# Li_Power_Boost_Converter.net
KiCad netlist of a schematic drawn in EAGLE
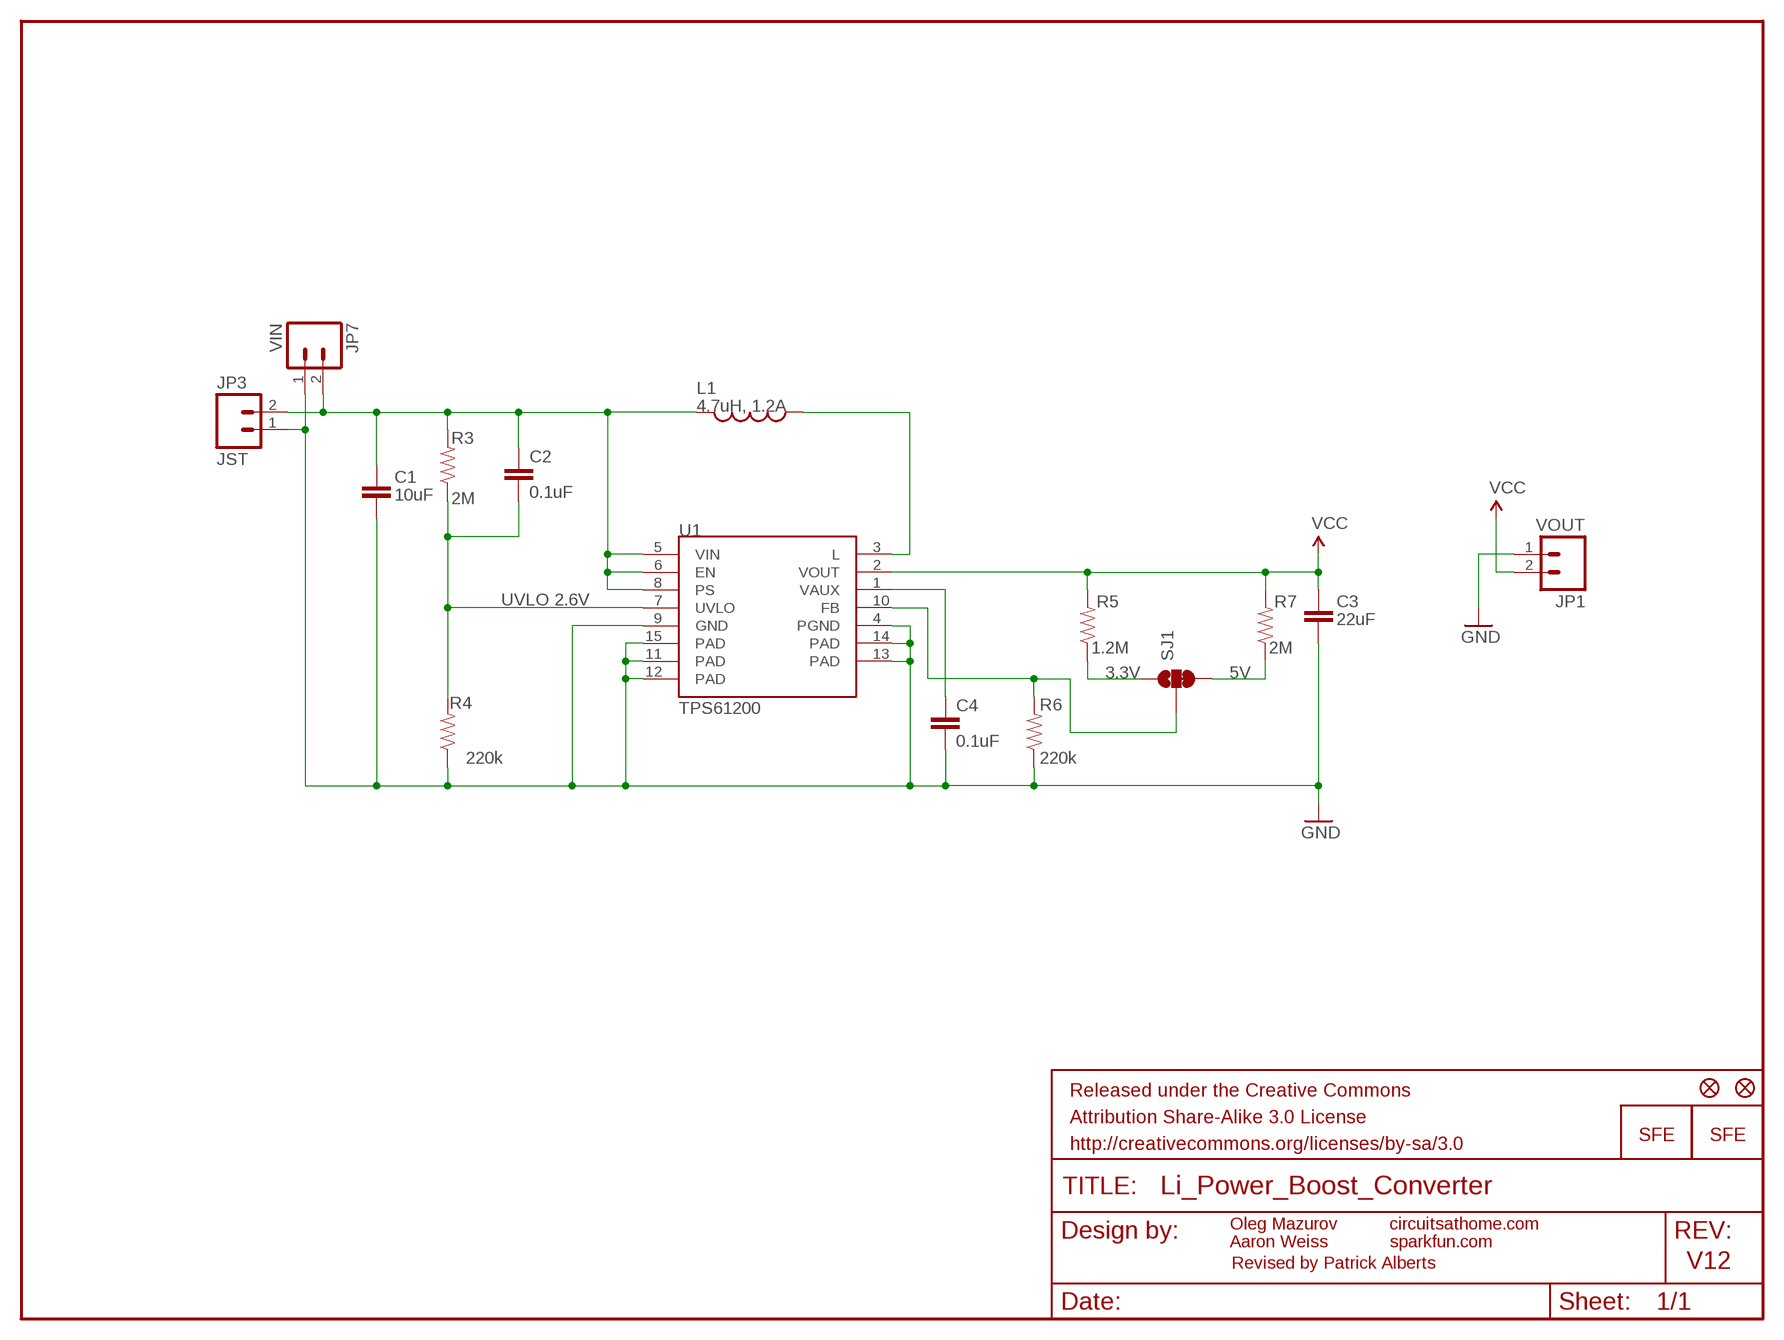
[diagram p0: schematic, sheet 1]

(export (version "E")
  (design (tool "Eeschema 10.0.6"))
  (components
    (comp (ref "C1")
      (value "10uF")
      (footprint "eagle-import:1206")
      (libsource (lib "eagle-import") (part "CAP1206"))
    )
    (comp (ref "C2")
      (value "0.1uF")
      (footprint "eagle-import:0603-CAP")
      (libsource (lib "eagle-import") (part "CAP0603-CAP"))
    )
    (comp (ref "C3")
      (value "22uF")
      (footprint "eagle-import:0805")
      (libsource (lib "eagle-import") (part "CAP0805"))
    )
    (comp (ref "C4")
      (value "0.1uF")
      (footprint "eagle-import:0603-CAP")
      (libsource (lib "eagle-import") (part "CAP0603-CAP"))
    )
    (comp (ref "FRAME1")
      (value "FRAME-LETTER")
      (footprint "eagle-import:CREATIVE_COMMONS")
      (libsource (lib "eagle-import") (part "FRAME-LETTER"))
    )
    (comp (ref "JP1")
      (value "VOUT")
      (footprint "eagle-import:1X02")
      (libsource (lib "eagle-import") (part "M02PTH"))
    )
    (comp (ref "JP2")
      (value "LOGO-SFESK")
      (footprint "eagle-import:SFE-LOGO-FLAME")
      (libsource (lib "eagle-import") (part "LOGO-SFESK"))
    )
    (comp (ref "JP3")
      (value "JST")
      (footprint "eagle-import:JST-2-SMD")
      (libsource (lib "eagle-import") (part "M02-JST-2MM-SMT"))
    )
    (comp (ref "JP4")
      (value "FIDUCIAL1X2")
      (footprint "eagle-import:FIDUCIAL-1X2")
      (libsource (lib "eagle-import") (part "FIDUCIAL1X2"))
    )
    (comp (ref "JP5")
      (value "FIDUCIAL1X2")
      (footprint "eagle-import:FIDUCIAL-1X2")
      (libsource (lib "eagle-import") (part "FIDUCIAL1X2"))
    )
    (comp (ref "JP6")
      (value "LOGO-SFENEW")
      (footprint "eagle-import:SFE-NEW-WEBLOGO")
      (libsource (lib "eagle-import") (part "LOGO-SFENEW"))
    )
    (comp (ref "JP7")
      (value "VIN")
      (footprint "eagle-import:1X02")
      (libsource (lib "eagle-import") (part "M02PTH"))
    )
    (comp (ref "L1")
      (value "4.7uH, 1.2A")
      (footprint "eagle-import:CDRH2D09")
      (libsource (lib "eagle-import") (part "INDUCTOR."))
    )
    (comp (ref "R3")
      (value "2M")
      (footprint "eagle-import:0603-RES")
      (libsource (lib "eagle-import") (part "RESISTOR0603-RES"))
    )
    (comp (ref "R4")
      (value "220k")
      (footprint "eagle-import:0603-RES")
      (libsource (lib "eagle-import") (part "RESISTOR0603-RES"))
    )
    (comp (ref "R5")
      (value "1.2M")
      (footprint "eagle-import:0603-RES")
      (libsource (lib "eagle-import") (part "RESISTOR0603-RES"))
    )
    (comp (ref "R6")
      (value "220k")
      (footprint "eagle-import:0603-RES")
      (libsource (lib "eagle-import") (part "RESISTOR0603-RES"))
    )
    (comp (ref "R7")
      (value "2M")
      (footprint "eagle-import:0603-RES")
      (libsource (lib "eagle-import") (part "RESISTOR0603-RES"))
    )
    (comp (ref "SJ1")
      (value "SOLDERJUMPER_2WAYPASTE2&3")
      (footprint "eagle-import:SJ_3_PASTE2&3")
      (libsource (lib "eagle-import") (part "SOLDERJUMPER_2WAYPASTE2&3"))
    )
    (comp (ref "U1")
      (value "TPS61200")
      (footprint "eagle-import:QFN-10_PAD")
      (libsource (lib "eagle-import") (part "TPS61200"))
    )
  )
  (nets
    (net (code "1") (name "/3.3V") (class "Default")
      (node (ref "R5") (pin "1") (pinfunction "1_1") (pintype "passive"))
      (node (ref "SJ1") (pin "1") (pinfunction "1_1") (pintype "passive"))
    )
    (net (code "2") (name "/5V") (class "Default")
      (node (ref "R7") (pin "1") (pinfunction "1_1") (pintype "passive"))
      (node (ref "SJ1") (pin "3") (pinfunction "3_3") (pintype "passive"))
    )
    (net (code "3") (name "GND") (class "Default")
      (node (ref "C1") (pin "2") (pinfunction "2_2") (pintype "passive"))
      (node (ref "C3") (pin "2") (pinfunction "2_2") (pintype "passive"))
      (node (ref "C4") (pin "2") (pinfunction "2_2") (pintype "passive"))
      (node (ref "JP1") (pin "1") (pinfunction "1_1") (pintype "passive"))
      (node (ref "JP3") (pin "1") (pinfunction "1_1") (pintype "passive"))
      (node (ref "JP7") (pin "1") (pinfunction "1_1") (pintype "passive"))
      (node (ref "R4") (pin "1") (pinfunction "1_1") (pintype "passive"))
      (node (ref "R6") (pin "1") (pinfunction "1_1") (pintype "passive"))
      (node (ref "U1") (pin "11") (pinfunction "PAD_11") (pintype "power_in"))
      (node (ref "U1") (pin "12") (pinfunction "PAD_12") (pintype "power_in"))
      (node (ref "U1") (pin "13") (pinfunction "PAD_13") (pintype "power_in"))
      (node (ref "U1") (pin "14") (pinfunction "PAD_14") (pintype "power_in"))
      (node (ref "U1") (pin "15") (pinfunction "PAD_15") (pintype "power_in"))
      (node (ref "U1") (pin "4") (pinfunction "PGND_4") (pintype "power_in"))
      (node (ref "U1") (pin "9") (pinfunction "GND_9") (pintype "power_in"))
    )
    (net (code "4") (name "Net-(L1-1)") (class "Default")
      (node (ref "L1") (pin "P$1") (pinfunction "1_P$1") (pintype "passive"))
      (node (ref "U1") (pin "3") (pinfunction "L_3") (pintype "passive"))
    )
    (net (code "5") (name "Net-(L1-2)") (class "Default")
      (node (ref "C1") (pin "1") (pinfunction "1_1") (pintype "passive"))
      (node (ref "C2") (pin "1") (pinfunction "1_1") (pintype "passive"))
      (node (ref "JP3") (pin "2") (pinfunction "2_2") (pintype "passive"))
      (node (ref "JP7") (pin "2") (pinfunction "2_2") (pintype "passive"))
      (node (ref "L1") (pin "P$2") (pinfunction "2_P$2") (pintype "passive"))
      (node (ref "R3") (pin "2") (pinfunction "2_2") (pintype "passive"))
      (node (ref "U1") (pin "5") (pinfunction "VIN_5") (pintype "power_in"))
      (node (ref "U1") (pin "6") (pinfunction "EN_6") (pintype "input"))
      (node (ref "U1") (pin "8") (pinfunction "PS_8") (pintype "input"))
    )
    (net (code "6") (name "Net-(U1-FB)") (class "Default")
      (node (ref "R6") (pin "2") (pinfunction "2_2") (pintype "passive"))
      (node (ref "SJ1") (pin "2") (pinfunction "2_2") (pintype "passive"))
      (node (ref "U1") (pin "10") (pinfunction "FB_10") (pintype "passive"))
    )
    (net (code "7") (name "Net-(U1-UVLO)") (class "Default")
      (node (ref "C2") (pin "2") (pinfunction "2_2") (pintype "passive"))
      (node (ref "R3") (pin "1") (pinfunction "1_1") (pintype "passive"))
      (node (ref "R4") (pin "2") (pinfunction "2_2") (pintype "passive"))
      (node (ref "U1") (pin "7") (pinfunction "UVLO_7") (pintype "passive"))
    )
    (net (code "8") (name "Net-(U1-VAUX)") (class "Default")
      (node (ref "C4") (pin "1") (pinfunction "1_1") (pintype "passive"))
      (node (ref "U1") (pin "1") (pinfunction "VAUX_1") (pintype "passive"))
    )
    (net (code "9") (name "VCC") (class "Default")
      (node (ref "C3") (pin "1") (pinfunction "1_1") (pintype "passive"))
      (node (ref "JP1") (pin "2") (pinfunction "2_2") (pintype "passive"))
      (node (ref "R5") (pin "2") (pinfunction "2_2") (pintype "passive"))
      (node (ref "R7") (pin "2") (pinfunction "2_2") (pintype "passive"))
      (node (ref "U1") (pin "2") (pinfunction "VOUT_2") (pintype "passive"))
    )
  )
)
